# design.net
KiCad netlist of a schematic drawn in Altium Designer
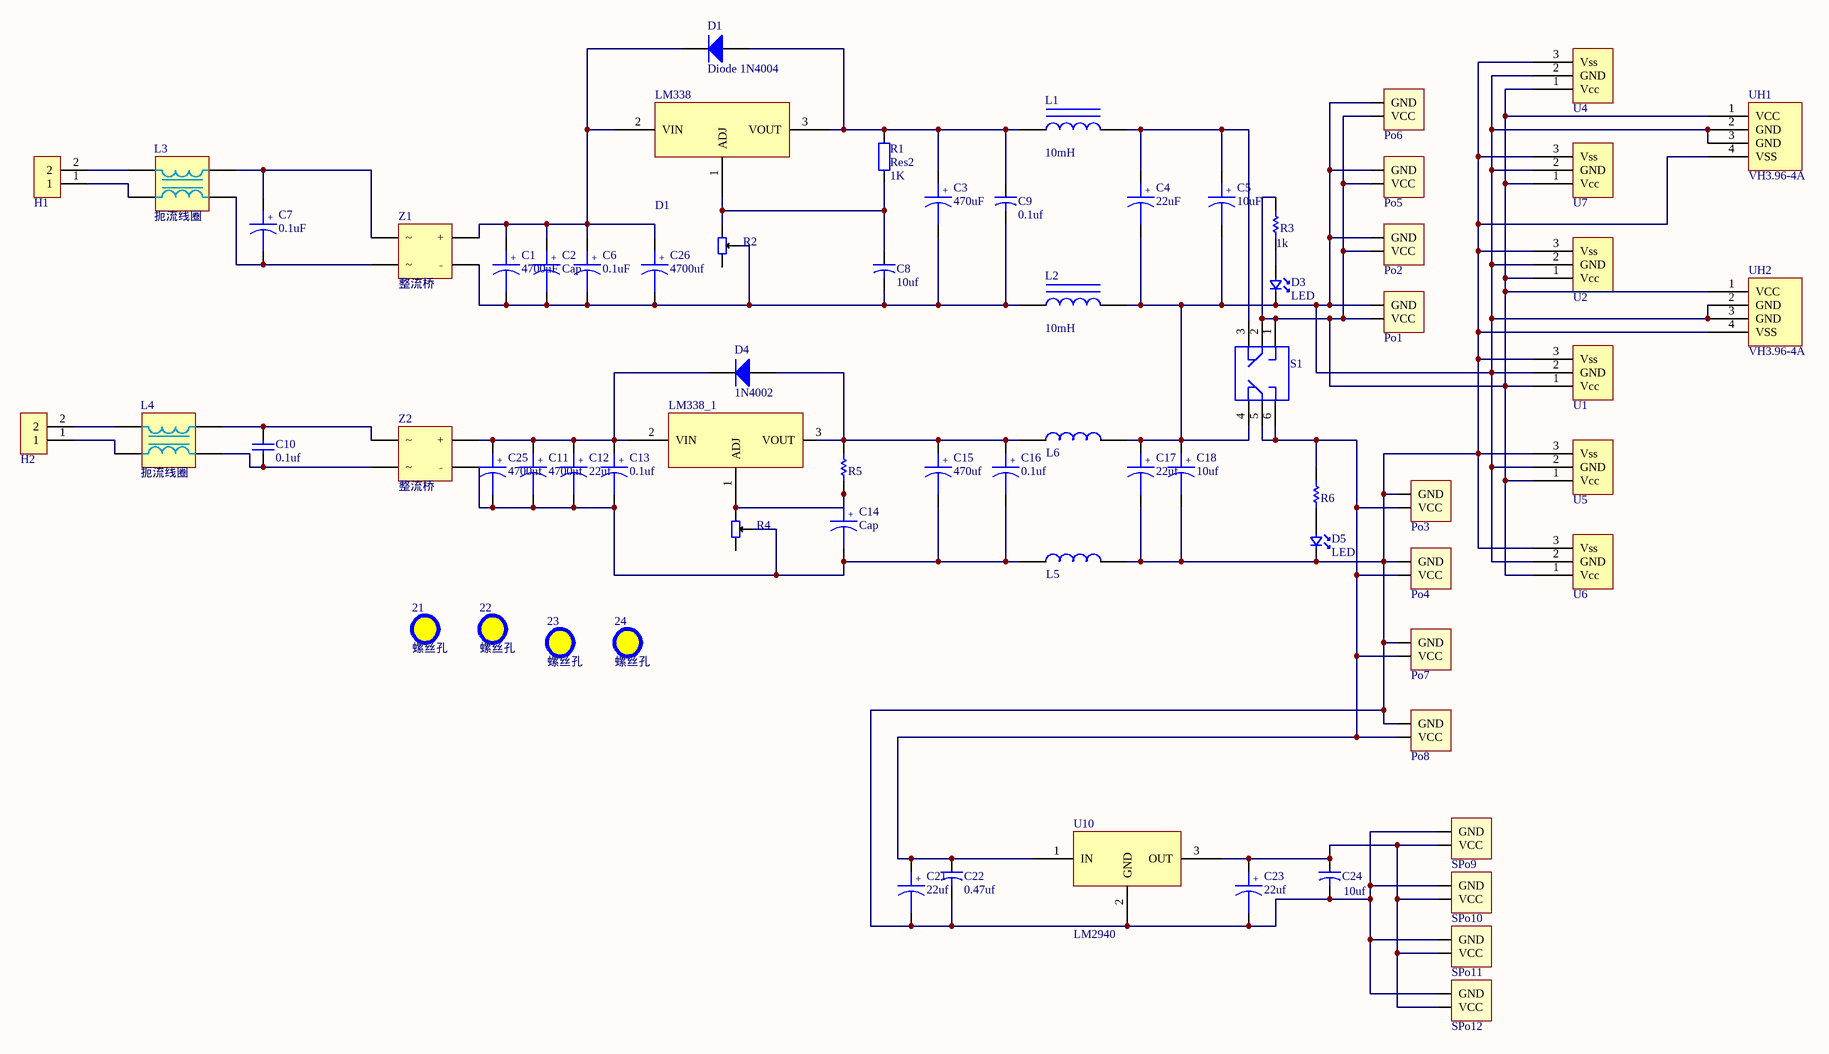
[diagram p0: 电源.SchDoc]

(export (version "E")
  (design (tool "Eeschema 10.0.6"))
  (components
    (comp (ref "21") (value "螺丝孔") (footprint "固定过孔") (libsource (lib "电源") (part "螺丝孔")))
    (comp (ref "22") (value "螺丝孔") (footprint "固定过孔") (libsource (lib "电源") (part "螺丝孔")))
    (comp (ref "23") (value "螺丝孔") (footprint "固定过孔") (libsource (lib "电源") (part "螺丝孔")))
    (comp (ref "24") (value "螺丝孔") (footprint "固定过孔") (libsource (lib "电源") (part "螺丝孔")))
    (comp (ref "C1") (value "4700uF") (footprint "CD-7.6mm") (libsource (lib "电源") (part "Cap")))
    (comp (ref "C2") (value "Cap") (footprint "CD-2.2mm") (libsource (lib "电源") (part "Cap")))
    (comp (ref "C3") (value "470uF") (footprint "CD-5mm") (libsource (lib "电源") (part "Cap")))
    (comp (ref "C4") (value "22uF") (footprint "CD-2.2mm") (libsource (lib "电源") (part "Cap")))
    (comp (ref "C5") (value "10uF") (footprint "陶瓷电容") (libsource (lib "电源") (part "Cap")))
    (comp (ref "C6") (value "0.1uF") (footprint "独石电容") (libsource (lib "电源") (part "Cap")))
    (comp (ref "C7") (value "0.1uF") (footprint "安规电容") (libsource (lib "电源") (part "Cap")))
    (comp (ref "C8")
      (value "Cap")
      (footprint "陶瓷电容")
      (fields (field (name "值") "10uf"))
      (libsource (lib "电源") (part "Cap_1"))
    )
    (comp (ref "C9")
      (value "Cap")
      (footprint "陶瓷电容")
      (fields (field (name "值") "0.1uf"))
      (libsource (lib "电源") (part "Cap_1"))
    )
    (comp (ref "C10")
      (value "Cap1")
      (footprint "安规电容")
      (fields (field (name "值") "0.1uf"))
      (libsource (lib "电源") (part "Cap1"))
    )
    (comp (ref "C11") (value "4700uf") (footprint "CD-7.6mm") (libsource (lib "电源") (part "Cap")))
    (comp (ref "C12") (value "22uf") (footprint "CD-2.2mm") (libsource (lib "电源") (part "Cap")))
    (comp (ref "C13") (value "0.1uf") (footprint "独石电容") (libsource (lib "电源") (part "Cap")))
    (comp (ref "C14") (value "Cap") (footprint "陶瓷电容") (libsource (lib "电源") (part "Cap")))
    (comp (ref "C15") (value "470uf") (footprint "CD-5mm") (libsource (lib "电源") (part "Cap")))
    (comp (ref "C16") (value "0.1uf") (footprint "陶瓷电容") (libsource (lib "电源") (part "Cap")))
    (comp (ref "C17") (value "22uf") (footprint "CD-2.2mm") (libsource (lib "电源") (part "Cap")))
    (comp (ref "C18") (value "10uf") (footprint "陶瓷电容") (libsource (lib "电源") (part "Cap")))
    (comp (ref "C21") (value "22uf") (footprint "CD-2.2mm") (libsource (lib "电源") (part "Cap")))
    (comp (ref "C22")
      (value "Cap")
      (footprint "陶瓷电容")
      (fields (field (name "值") "0.47uf"))
      (libsource (lib "电源") (part "Cap_1"))
    )
    (comp (ref "C23") (value "22uf") (footprint "CD-2.2mm") (libsource (lib "电源") (part "Cap")))
    (comp (ref "C24")
      (value "Cap")
      (footprint "陶瓷电容")
      (fields (field (name "值") "10uf"))
      (libsource (lib "电源") (part "Cap_1"))
    )
    (comp (ref "C25") (value "4700uf") (footprint "CD-7.6mm") (libsource (lib "电源") (part "Cap")))
    (comp (ref "C26") (value "4700uf") (footprint "CD-7.6mm") (libsource (lib "电源") (part "Cap")))
    (comp (ref "D1")
      (value "Diode 1N4004")
      (footprint "SMC")
      (description "1 Amp General Purpose Rectifier")
      (fields (field (name "PUBLISHER") "Altium Limited"))
      (libsource (lib "Miscellaneous Devices") (part "Diode 1N4004"))
    )
    (comp (ref "D3") (value "LED") (footprint "0805_s") (libsource (lib "电源") (part "LED")))
    (comp (ref "D4")
      (value "1N4002")
      (footprint "SMC")
      (description "Default Diode")
      (fields (field (name "PUBLISHER") "Altium Limited"))
      (libsource (lib "电源") (part "Diode"))
    )
    (comp (ref "D5") (value "LED") (footprint "0805_s") (libsource (lib "电源") (part "LED")))
    (comp (ref "H1") (value "HT3.96-2P") (footprint "HT39.6-2P-S") (libsource (lib "电源") (part "HT3.96-2P")))
    (comp (ref "H2") (value "HT3.96-2P") (footprint "HT39.6-2P-S") (libsource (lib "电源") (part "HT3.96-2P")))
    (comp (ref "L1")
      (value "10mH")
      (footprint "功率电感-12x12 - duplicate")
      (description "Magnetic-Core Inductor")
      (fields (field (name "Comment") "Inductor Iron") (field (name "PUBLISHER") "Altium Limited"))
      (libsource (lib "Miscellaneous Devices") (part "Inductor Iron"))
    )
    (comp (ref "L2")
      (value "10mH")
      (footprint "功率电感-12x12 - duplicate")
      (description "Magnetic-Core Inductor")
      (fields (field (name "Comment") "Inductor Iron") (field (name "PUBLISHER") "Altium Limited"))
      (libsource (lib "Miscellaneous Devices") (part "Inductor Iron"))
    )
    (comp (ref "L3") (value "扼流线圈") (footprint "扼流线圈") (libsource (lib "电源") (part "扼流线圈")))
    (comp (ref "L4") (value "扼流线圈") (footprint "扼流线圈") (libsource (lib "电源") (part "扼流线圈")))
    (comp (ref "L5") (value "SMD") (footprint "功率电感-12x12 - duplicate") (libsource (lib "电源") (part "功率电感")))
    (comp (ref "L6") (value "SMD") (footprint "功率电感-12x12 - duplicate") (libsource (lib "电源") (part "功率电感")))
    (comp (ref "LM338") (value "D1") (footprint "LM338") (libsource (lib "电源") (part "LM338")))
    (comp (ref "LM338_1") (value "~") (footprint "LM338") (libsource (lib "电源") (part "LM338")))
    (comp (ref "Po1")
      (value "Power_2Port")
      (footprint "Power_S_2Port")
      (libsource (lib "电源") (part "Power_2Port"))
    )
    (comp (ref "Po2")
      (value "Power_2Port")
      (footprint "Power_S_2Port")
      (libsource (lib "电源") (part "Power_2Port"))
    )
    (comp (ref "Po3")
      (value "Power_2Port")
      (footprint "Power_S_2Port")
      (libsource (lib "电源") (part "Power_2Port"))
    )
    (comp (ref "Po4")
      (value "Power_2Port")
      (footprint "Power_S_2Port")
      (libsource (lib "电源") (part "Power_2Port"))
    )
    (comp (ref "Po5")
      (value "Power_2Port")
      (footprint "Power_S_2Port")
      (libsource (lib "电源") (part "Power_2Port"))
    )
    (comp (ref "Po6")
      (value "Power_2Port")
      (footprint "Power_S_2Port")
      (libsource (lib "电源") (part "Power_2Port"))
    )
    (comp (ref "Po7")
      (value "Power_2Port")
      (footprint "Power_S_2Port")
      (libsource (lib "电源") (part "Power_2Port"))
    )
    (comp (ref "Po8")
      (value "Power_2Port")
      (footprint "Power_S_2Port")
      (libsource (lib "电源") (part "Power_2Port"))
    )
    (comp (ref "R1")
      (value "Res2")
      (footprint "0805")
      (description "Resistor")
      (fields (field (name "ALTIUM_VALUE") "1K") (field (name "PUBLISHER") "Altium Limited"))
      (libsource (lib "Miscellaneous Devices") (part "Res2"))
    )
    (comp (ref "R2") (value "可调电位器1") (footprint "电位器") (libsource (lib "电源") (part "可调电位器1")))
    (comp (ref "R3") (value "1k") (footprint "0805") (description "1K") (libsource (lib "电源") (part "RES")))
    (comp (ref "R4") (value "可调电位器1") (footprint "电位器") (libsource (lib "电源") (part "可调电位器1")))
    (comp (ref "R5") (value "RES") (footprint "0805") (libsource (lib "电源") (part "RES")))
    (comp (ref "R6") (value "RES") (footprint "0805") (libsource (lib "电源") (part "RES")))
    (comp (ref "S1") (value "双掷开关") (footprint "SWITCH") (libsource (lib "电源") (part "双掷开关")))
    (comp (ref "SPo9")
      (value "Power_2Port")
      (footprint "Power_S_2Port")
      (libsource (lib "电源") (part "Power_2Port"))
    )
    (comp (ref "SPo10")
      (value "Power_2Port")
      (footprint "Power_S_2Port")
      (libsource (lib "电源") (part "Power_2Port"))
    )
    (comp (ref "SPo11")
      (value "Power_2Port")
      (footprint "Power_S_2Port")
      (libsource (lib "电源") (part "Power_2Port"))
    )
    (comp (ref "SPo12")
      (value "Power_2Port")
      (footprint "Power_S_2Port")
      (libsource (lib "电源") (part "Power_2Port"))
    )
    (comp (ref "U1") (value "XH2.54-3p") (footprint "XH2.54-3p") (libsource (lib "电源") (part "XH2.54-3p")))
    (comp (ref "U2") (value "XH2.54-3p") (footprint "XH2.54-3p") (libsource (lib "电源") (part "XH2.54-3p")))
    (comp (ref "U4") (value "XH2.54-3p") (footprint "XH2.54-3p") (libsource (lib "电源") (part "XH2.54-3p")))
    (comp (ref "U5") (value "XH2.54-3p") (footprint "XH2.54-3p") (libsource (lib "电源") (part "XH2.54-3p")))
    (comp (ref "U6") (value "XH2.54-3p") (footprint "XH2.54-3p") (libsource (lib "电源") (part "XH2.54-3p")))
    (comp (ref "U7") (value "XH2.54-3p") (footprint "XH2.54-3p") (libsource (lib "电源") (part "XH2.54-3p")))
    (comp (ref "U10") (value "LM2940") (footprint "TO-220") (libsource (lib "电源") (part "LM2940")))
    (comp (ref "UH1") (value "VH3.96-4A") (footprint "VH3.96-4P") (libsource (lib "电源") (part "VH3.96-4A")))
    (comp (ref "UH2") (value "VH3.96-4A") (footprint "VH3.96-4P") (libsource (lib "电源") (part "VH3.96-4A")))
    (comp (ref "Z1") (value "整流桥") (footprint "整流桥") (libsource (lib "电源") (part "整流桥")))
    (comp (ref "Z2") (value "整流桥") (footprint "整流桥") (libsource (lib "电源") (part "整流桥")))
  )
  (nets
    (net (code "1") (name "Net-(C4-Pad1)") (class "Default")
      (node (ref "C4") (pin "1") (pinfunction "1_1") (pintype "passive"))
      (node (ref "C5") (pin "1") (pinfunction "1_1") (pintype "passive"))
      (node (ref "L1") (pin "2") (pinfunction "2_2") (pintype "passive"))
      (node (ref "S1") (pin "3") (pinfunction "3_3") (pintype "passive"))
    )
    (net (code "2") (name "Net-(C7-Pad1)") (class "Default")
      (node (ref "C7") (pin "1") (pinfunction "1_1") (pintype "passive"))
      (node (ref "L3") (pin "2") (pinfunction "2_2") (pintype "passive"))
      (node (ref "Z1") (pin "2") (pinfunction "~_2") (pintype "passive"))
    )
    (net (code "3") (name "Net-(C7-Pad2)") (class "Default")
      (node (ref "C7") (pin "2") (pinfunction "2_2") (pintype "passive"))
      (node (ref "L3") (pin "3") (pinfunction "3_3") (pintype "passive"))
      (node (ref "Z1") (pin "3") (pinfunction "~_3") (pintype "passive"))
    )
    (net (code "4") (name "Net-(C10-Pad1)") (class "Default")
      (node (ref "C10") (pin "1") (pinfunction "1_1") (pintype "passive"))
      (node (ref "L4") (pin "3") (pinfunction "3_3") (pintype "passive"))
      (node (ref "Z2") (pin "3") (pinfunction "~_3") (pintype "passive"))
    )
    (net (code "5") (name "Net-(C10-Pad2)") (class "Default")
      (node (ref "C10") (pin "2") (pinfunction "2_2") (pintype "passive"))
      (node (ref "L4") (pin "2") (pinfunction "2_2") (pintype "passive"))
      (node (ref "Z2") (pin "2") (pinfunction "~_2") (pintype "passive"))
    )
    (net (code "6") (name "Net-(D1-A)") (class "Default")
      (node (ref "C3") (pin "1") (pinfunction "1_1") (pintype "passive"))
      (node (ref "C9") (pin "1") (pinfunction "1_1") (pintype "passive"))
      (node (ref "D1") (pin "1") (pinfunction "A_1") (pintype "passive"))
      (node (ref "L1") (pin "1") (pinfunction "1_1") (pintype "passive"))
      (node (ref "LM338") (pin "3") (pinfunction "VOUT_3") (pintype "passive"))
      (node (ref "R1") (pin "2") (pinfunction "2_2") (pintype "passive"))
    )
    (net (code "7") (name "Net-(D1-K)") (class "Default")
      (node (ref "C1") (pin "1") (pinfunction "1_1") (pintype "passive"))
      (node (ref "C2") (pin "1") (pinfunction "1_1") (pintype "passive"))
      (node (ref "C26") (pin "1") (pinfunction "1_1") (pintype "passive"))
      (node (ref "C6") (pin "1") (pinfunction "1_1") (pintype "passive"))
      (node (ref "D1") (pin "2") (pinfunction "K_2") (pintype "passive"))
      (node (ref "LM338") (pin "2") (pinfunction "VIN_2") (pintype "passive"))
      (node (ref "Z1") (pin "1") (pinfunction "+_1") (pintype "passive"))
    )
    (net (code "8") (name "Net-(D3-Pad2)") (class "Default")
      (node (ref "D3") (pin "2") (pinfunction "2_2") (pintype "passive"))
      (node (ref "R3") (pin "1") (pinfunction "1_1") (pintype "passive"))
    )
    (net (code "9") (name "Net-(D4-A)") (class "Default")
      (node (ref "C15") (pin "1") (pinfunction "1_1") (pintype "passive"))
      (node (ref "C16") (pin "1") (pinfunction "1_1") (pintype "passive"))
      (node (ref "D4") (pin "1") (pinfunction "A_1") (pintype "passive"))
      (node (ref "L6") (pin "1") (pintype "passive"))
      (node (ref "LM338_1") (pin "3") (pinfunction "VOUT_3") (pintype "passive"))
      (node (ref "R5") (pin "2") (pinfunction "2_2") (pintype "passive"))
    )
    (net (code "10") (name "Net-(D4-K)") (class "Default")
      (node (ref "C11") (pin "1") (pinfunction "1_1") (pintype "passive"))
      (node (ref "C12") (pin "1") (pinfunction "1_1") (pintype "passive"))
      (node (ref "C13") (pin "1") (pinfunction "1_1") (pintype "passive"))
      (node (ref "C25") (pin "1") (pinfunction "1_1") (pintype "passive"))
      (node (ref "D4") (pin "2") (pinfunction "K_2") (pintype "passive"))
      (node (ref "LM338_1") (pin "2") (pinfunction "VIN_2") (pintype "passive"))
      (node (ref "Z2") (pin "1") (pinfunction "+_1") (pintype "passive"))
    )
    (net (code "11") (name "Net-(D5-Pad2)") (class "Default")
      (node (ref "D5") (pin "2") (pinfunction "2_2") (pintype "passive"))
      (node (ref "R6") (pin "1") (pinfunction "1_1") (pintype "passive"))
    )
    (net (code "12") (name "Net-(H1-Pad1)") (class "Default")
      (node (ref "H1") (pin "1") (pinfunction "1_1") (pintype "passive"))
      (node (ref "L3") (pin "4") (pinfunction "4_4") (pintype "passive"))
    )
    (net (code "13") (name "Net-(H1-Pad2)") (class "Default")
      (node (ref "H1") (pin "2") (pinfunction "2_2") (pintype "passive"))
      (node (ref "L3") (pin "1") (pinfunction "1_1") (pintype "passive"))
    )
    (net (code "14") (name "Net-(H2-Pad1)") (class "Default")
      (node (ref "H2") (pin "1") (pinfunction "1_1") (pintype "passive"))
      (node (ref "L4") (pin "4") (pinfunction "4_4") (pintype "passive"))
    )
    (net (code "15") (name "Net-(H2-Pad2)") (class "Default")
      (node (ref "H2") (pin "2") (pinfunction "2_2") (pintype "passive"))
      (node (ref "L4") (pin "1") (pinfunction "1_1") (pintype "passive"))
    )
    (net (code "16") (name "Net-(LM338-ADJ)") (class "Default")
      (node (ref "C8") (pin "1") (pinfunction "1_1") (pintype "passive"))
      (node (ref "LM338") (pin "1") (pinfunction "ADJ_1") (pintype "passive"))
      (node (ref "R1") (pin "1") (pinfunction "1_1") (pintype "passive"))
      (node (ref "R2") (pin "3") (pinfunction "3_3") (pintype "passive"))
    )
    (net (code "17") (name "Net-(LM338_1-ADJ)") (class "Default")
      (node (ref "C14") (pin "1") (pinfunction "1_1") (pintype "passive"))
      (node (ref "LM338_1") (pin "1") (pinfunction "ADJ_1") (pintype "passive"))
      (node (ref "R4") (pin "3") (pinfunction "3_3") (pintype "passive"))
      (node (ref "R5") (pin "1") (pinfunction "1_1") (pintype "passive"))
    )
    (net (code "18") (name "Net-(Po1-GND)") (class "Default")
      (node (ref "C17") (pin "1") (pinfunction "1_1") (pintype "passive"))
      (node (ref "C18") (pin "1") (pinfunction "1_1") (pintype "passive"))
      (node (ref "C4") (pin "2") (pinfunction "2_2") (pintype "passive"))
      (node (ref "C5") (pin "2") (pinfunction "2_2") (pintype "passive"))
      (node (ref "D3") (pin "1") (pinfunction "1_1") (pintype "passive"))
      (node (ref "L2") (pin "2") (pinfunction "2_2") (pintype "passive"))
      (node (ref "L6") (pin "2") (pintype "passive"))
      (node (ref "Po1") (pin "2") (pinfunction "GND_2") (pintype "passive"))
      (node (ref "Po2") (pin "2") (pinfunction "GND_2") (pintype "passive"))
      (node (ref "Po5") (pin "2") (pinfunction "GND_2") (pintype "passive"))
      (node (ref "Po6") (pin "2") (pinfunction "GND_2") (pintype "passive"))
      (node (ref "S1") (pin "4") (pinfunction "4_4") (pintype "passive"))
      (node (ref "U1") (pin "2") (pinfunction "GND_2") (pintype "passive"))
      (node (ref "U2") (pin "2") (pinfunction "GND_2") (pintype "passive"))
      (node (ref "U4") (pin "2") (pinfunction "GND_2") (pintype "passive"))
      (node (ref "U5") (pin "2") (pinfunction "GND_2") (pintype "passive"))
      (node (ref "U6") (pin "2") (pinfunction "GND_2") (pintype "passive"))
      (node (ref "U7") (pin "2") (pinfunction "GND_2") (pintype "passive"))
      (node (ref "UH1") (pin "2") (pinfunction "GND_2") (pintype "passive"))
      (node (ref "UH1") (pin "3") (pinfunction "GND_3") (pintype "passive"))
      (node (ref "UH2") (pin "2") (pinfunction "GND_2") (pintype "passive"))
      (node (ref "UH2") (pin "3") (pinfunction "GND_3") (pintype "passive"))
    )
    (net (code "19") (name "Net-(Po1-VCC)") (class "Default")
      (node (ref "Po1") (pin "1") (pinfunction "VCC_1") (pintype "passive"))
      (node (ref "Po2") (pin "1") (pinfunction "VCC_1") (pintype "passive"))
      (node (ref "Po5") (pin "1") (pinfunction "VCC_1") (pintype "passive"))
      (node (ref "Po6") (pin "1") (pinfunction "VCC_1") (pintype "passive"))
      (node (ref "R3") (pin "2") (pinfunction "2_2") (pintype "passive"))
      (node (ref "S1") (pin "1") (pinfunction "1_1") (pintype "passive"))
      (node (ref "S1") (pin "2") (pinfunction "2_2") (pintype "passive"))
      (node (ref "U1") (pin "1") (pinfunction "Vcc_1") (pintype "passive"))
      (node (ref "U2") (pin "1") (pinfunction "Vcc_1") (pintype "passive"))
      (node (ref "U4") (pin "1") (pinfunction "Vcc_1") (pintype "passive"))
      (node (ref "U5") (pin "1") (pinfunction "Vcc_1") (pintype "passive"))
      (node (ref "U6") (pin "1") (pinfunction "Vcc_1") (pintype "passive"))
      (node (ref "U7") (pin "1") (pinfunction "Vcc_1") (pintype "passive"))
      (node (ref "UH1") (pin "1") (pinfunction "VCC_1") (pintype "passive"))
      (node (ref "UH2") (pin "1") (pinfunction "VCC_1") (pintype "passive"))
    )
    (net (code "20") (name "Net-(Po3-GND)") (class "Default")
      (node (ref "C17") (pin "2") (pinfunction "2_2") (pintype "passive"))
      (node (ref "C18") (pin "2") (pinfunction "2_2") (pintype "passive"))
      (node (ref "C21") (pin "2") (pinfunction "2_2") (pintype "passive"))
      (node (ref "C22") (pin "2") (pinfunction "2_2") (pintype "passive"))
      (node (ref "C23") (pin "2") (pinfunction "2_2") (pintype "passive"))
      (node (ref "C24") (pin "2") (pinfunction "2_2") (pintype "passive"))
      (node (ref "D5") (pin "1") (pinfunction "1_1") (pintype "passive"))
      (node (ref "L5") (pin "2") (pintype "passive"))
      (node (ref "Po3") (pin "2") (pinfunction "GND_2") (pintype "passive"))
      (node (ref "Po4") (pin "2") (pinfunction "GND_2") (pintype "passive"))
      (node (ref "Po7") (pin "2") (pinfunction "GND_2") (pintype "passive"))
      (node (ref "Po8") (pin "2") (pinfunction "GND_2") (pintype "passive"))
      (node (ref "SPo10") (pin "2") (pinfunction "GND_2") (pintype "passive"))
      (node (ref "SPo11") (pin "2") (pinfunction "GND_2") (pintype "passive"))
      (node (ref "SPo12") (pin "2") (pinfunction "GND_2") (pintype "passive"))
      (node (ref "SPo9") (pin "2") (pinfunction "GND_2") (pintype "passive"))
      (node (ref "U1") (pin "3") (pinfunction "Vss_3") (pintype "passive"))
      (node (ref "U10") (pin "2") (pinfunction "GND_2") (pintype "passive"))
      (node (ref "U2") (pin "3") (pinfunction "Vss_3") (pintype "passive"))
      (node (ref "U4") (pin "3") (pinfunction "Vss_3") (pintype "passive"))
      (node (ref "U5") (pin "3") (pinfunction "Vss_3") (pintype "passive"))
      (node (ref "U6") (pin "3") (pinfunction "Vss_3") (pintype "passive"))
      (node (ref "U7") (pin "3") (pinfunction "Vss_3") (pintype "passive"))
      (node (ref "UH1") (pin "4") (pinfunction "VSS_4") (pintype "passive"))
      (node (ref "UH2") (pin "4") (pinfunction "VSS_4") (pintype "passive"))
    )
    (net (code "21") (name "Net-(Po3-VCC)") (class "Default")
      (node (ref "C21") (pin "1") (pinfunction "1_1") (pintype "passive"))
      (node (ref "C22") (pin "1") (pinfunction "1_1") (pintype "passive"))
      (node (ref "Po3") (pin "1") (pinfunction "VCC_1") (pintype "passive"))
      (node (ref "Po4") (pin "1") (pinfunction "VCC_1") (pintype "passive"))
      (node (ref "Po7") (pin "1") (pinfunction "VCC_1") (pintype "passive"))
      (node (ref "Po8") (pin "1") (pinfunction "VCC_1") (pintype "passive"))
      (node (ref "R6") (pin "2") (pinfunction "2_2") (pintype "passive"))
      (node (ref "S1") (pin "5") (pinfunction "5_5") (pintype "passive"))
      (node (ref "S1") (pin "6") (pinfunction "6_6") (pintype "passive"))
      (node (ref "U10") (pin "1") (pinfunction "IN_1") (pintype "passive"))
    )
    (net (code "22") (name "Net-(SPo10-VCC)") (class "Default")
      (node (ref "C23") (pin "1") (pinfunction "1_1") (pintype "passive"))
      (node (ref "C24") (pin "1") (pinfunction "1_1") (pintype "passive"))
      (node (ref "SPo10") (pin "1") (pinfunction "VCC_1") (pintype "passive"))
      (node (ref "SPo11") (pin "1") (pinfunction "VCC_1") (pintype "passive"))
      (node (ref "SPo12") (pin "1") (pinfunction "VCC_1") (pintype "passive"))
      (node (ref "SPo9") (pin "1") (pinfunction "VCC_1") (pintype "passive"))
      (node (ref "U10") (pin "3") (pinfunction "OUT_3") (pintype "passive"))
    )
    (net (code "23") (name "Net-(Z1-﹣)") (class "Default")
      (node (ref "C1") (pin "2") (pinfunction "2_2") (pintype "passive"))
      (node (ref "C2") (pin "2") (pinfunction "2_2") (pintype "passive"))
      (node (ref "C26") (pin "2") (pinfunction "2_2") (pintype "passive"))
      (node (ref "C3") (pin "2") (pinfunction "2_2") (pintype "passive"))
      (node (ref "C6") (pin "2") (pinfunction "2_2") (pintype "passive"))
      (node (ref "C8") (pin "2") (pinfunction "2_2") (pintype "passive"))
      (node (ref "C9") (pin "2") (pinfunction "2_2") (pintype "passive"))
      (node (ref "L2") (pin "1") (pinfunction "1_1") (pintype "passive"))
      (node (ref "R2") (pin "2") (pinfunction "2_2") (pintype "passive"))
      (node (ref "Z1") (pin "4") (pinfunction "﹣_4") (pintype "passive"))
    )
    (net (code "24") (name "Net-(Z2-﹣)") (class "Default")
      (node (ref "C11") (pin "2") (pinfunction "2_2") (pintype "passive"))
      (node (ref "C12") (pin "2") (pinfunction "2_2") (pintype "passive"))
      (node (ref "C13") (pin "2") (pinfunction "2_2") (pintype "passive"))
      (node (ref "C14") (pin "2") (pinfunction "2_2") (pintype "passive"))
      (node (ref "C15") (pin "2") (pinfunction "2_2") (pintype "passive"))
      (node (ref "C16") (pin "2") (pinfunction "2_2") (pintype "passive"))
      (node (ref "C25") (pin "2") (pinfunction "2_2") (pintype "passive"))
      (node (ref "L5") (pin "1") (pintype "passive"))
      (node (ref "R4") (pin "2") (pinfunction "2_2") (pintype "passive"))
      (node (ref "Z2") (pin "4") (pinfunction "﹣_4") (pintype "passive"))
    )
    (net (code "25") (name "unconnected-(R2-Pad1)") (class "Default")
      (node (ref "R2") (pin "1") (pinfunction "1_1") (pintype "passive"))
    )
    (net (code "26") (name "unconnected-(R4-Pad1)") (class "Default")
      (node (ref "R4") (pin "1") (pinfunction "1_1") (pintype "passive"))
    )
  )
)
